# Doormio.net
KiCad netlist of a schematic drawn in EAGLE
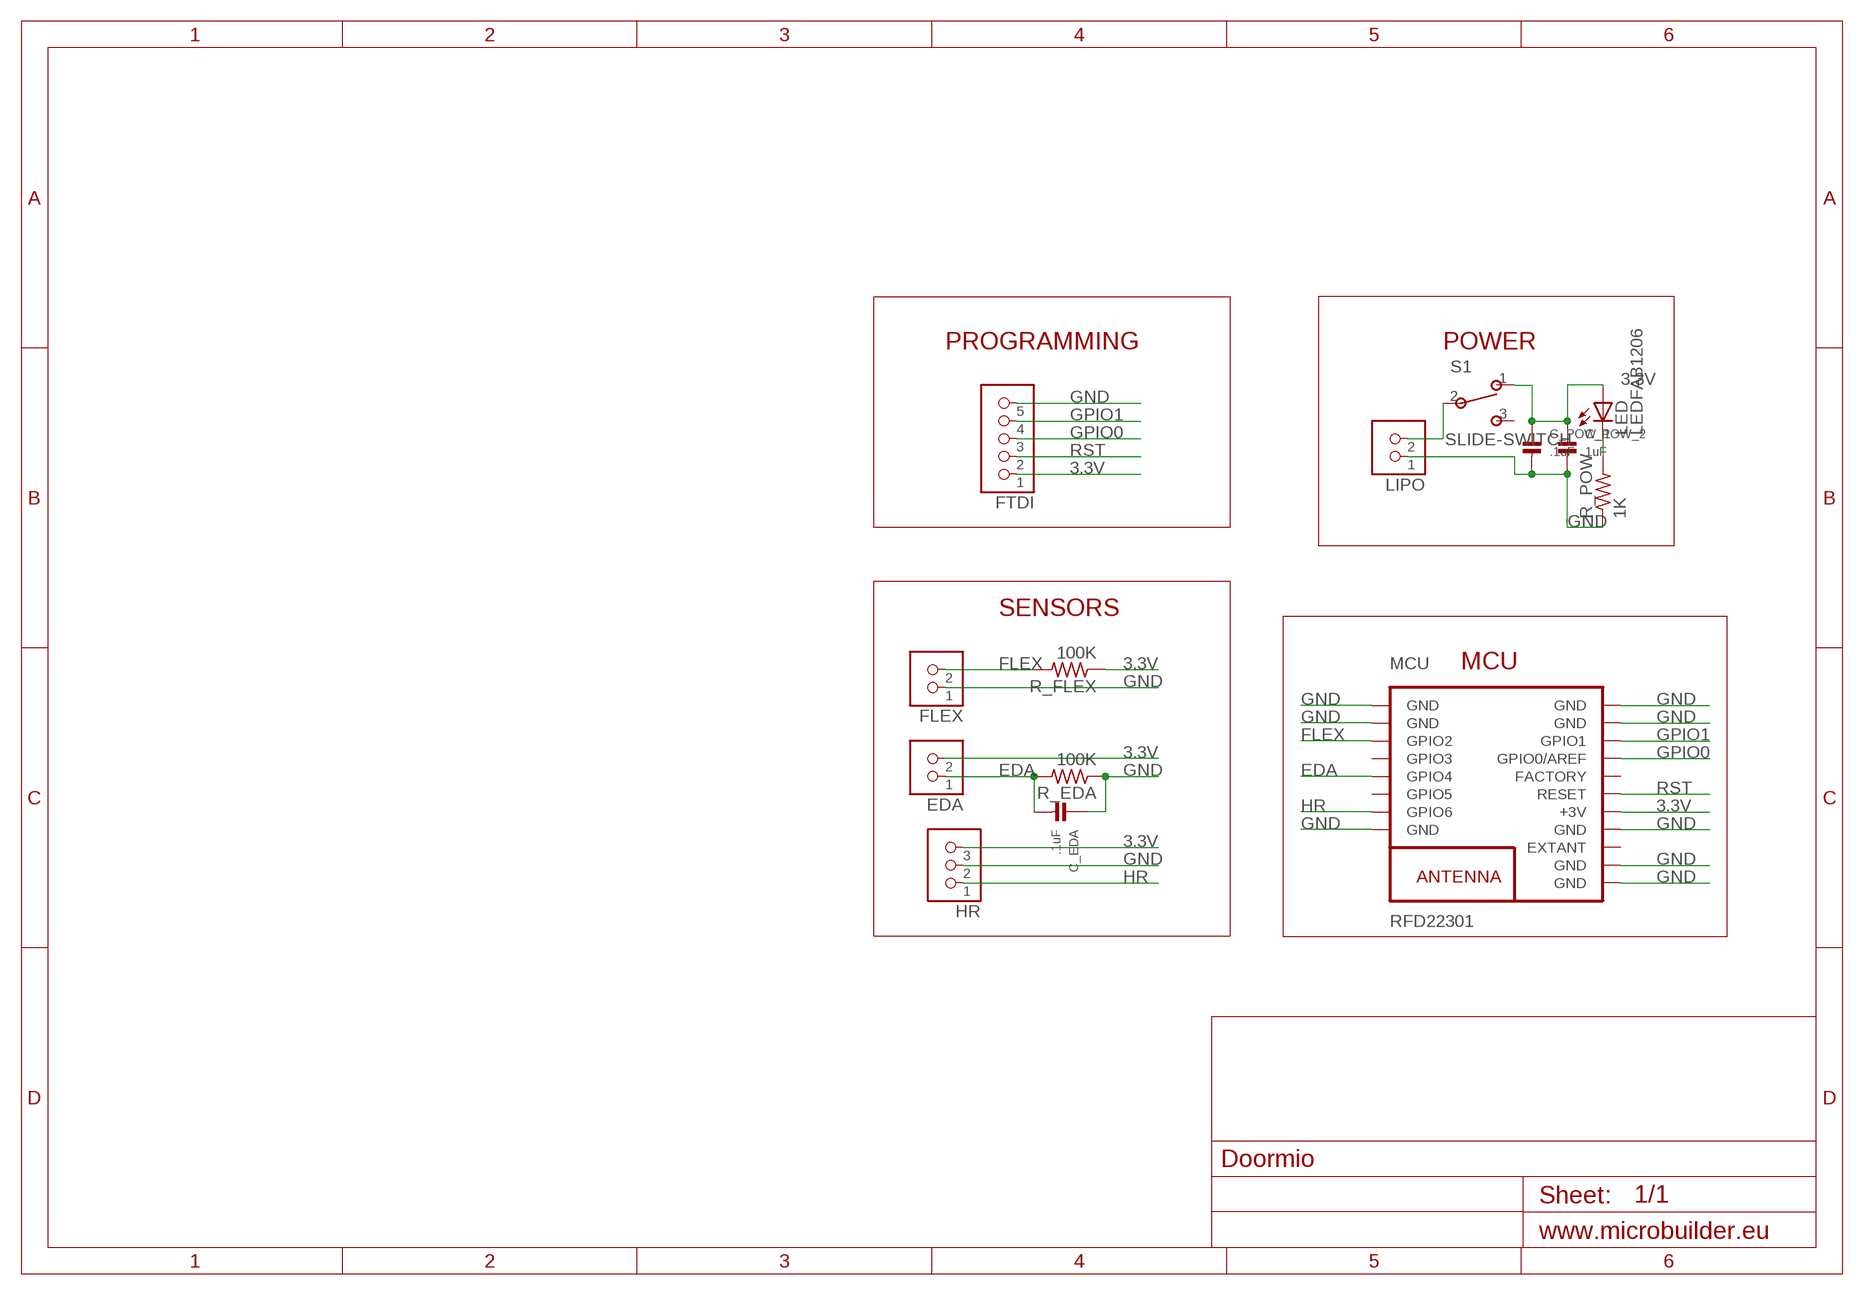
[diagram p0: schematic, sheet 1]

(export (version "E")
  (design (tool "Eeschema 10.0.6"))
  (components
    (comp (ref "C_EDA")
      (value ".1uF")
      (footprint "eagle-import:0603")
      (libsource (lib "eagle-import") (part "CAP_CERAMIC0603"))
    )
    (comp (ref "C_POW_1")
      (value ".1uF")
      (footprint "eagle-import:0603")
      (libsource (lib "eagle-import") (part "CAP_CERAMIC0603"))
    )
    (comp (ref "C_POW_2")
      (value "1uF")
      (footprint "eagle-import:0603")
      (libsource (lib "eagle-import") (part "CAP_CERAMIC0603"))
    )
    (comp (ref "EDA")
      (value "1X2-SMD-HEADER")
      (footprint "eagle-import:1X02SMD")
      (libsource (lib "eagle-import") (part "1X2-SMD-HEADER"))
    )
    (comp (ref "FLEX")
      (value "1X2-SMD-HEADER")
      (footprint "eagle-import:1X02SMD")
      (libsource (lib "eagle-import") (part "1X2-SMD-HEADER"))
    )
    (comp (ref "FTDI")
      (value "1X5-SMD-HEADER")
      (footprint "eagle-import:1X05SMD")
      (libsource (lib "eagle-import") (part "1X5-SMD-HEADER"))
    )
    (comp (ref "HR")
      (value "1X3-SMD-HEADER")
      (footprint "eagle-import:1X03SMD")
      (libsource (lib "eagle-import") (part "1X3-SMD-HEADER"))
    )
    (comp (ref "LED")
      (value "LEDFAB1206")
      (footprint "eagle-import:LED1206FAB")
      (libsource (lib "eagle-import") (part "LEDFAB1206"))
    )
    (comp (ref "LIPO")
      (value "1X2-SMD-HEADER")
      (footprint "eagle-import:1X02SMD")
      (libsource (lib "eagle-import") (part "1X2-SMD-HEADER"))
    )
    (comp (ref "MCU")
      (value "RFD22301")
      (footprint "eagle-import:RFD22301")
      (libsource (lib "eagle-import") (part "RFD22301"))
    )
    (comp (ref "R_EDA")
      (value "100K")
      (footprint "eagle-import:R0603")
      (libsource (lib "eagle-import") (part "R-US_R0603"))
    )
    (comp (ref "R_FLEX")
      (value "100K")
      (footprint "eagle-import:R0603")
      (libsource (lib "eagle-import") (part "R-US_R0603"))
    )
    (comp (ref "R_POW")
      (value "1K")
      (footprint "eagle-import:R0603")
      (libsource (lib "eagle-import") (part "R-US_R0603"))
    )
    (comp (ref "S1")
      (value "SLIDE-SWITCH")
      (footprint "eagle-import:AYZ0102AGRLC")
      (libsource (lib "eagle-import") (part "SLIDE-SWITCH"))
    )
  )
  (nets
    (net (code "1") (name "/3.3V") (class "Default")
      (node (ref "C_POW_1") (pin "1") (pinfunction "P$1_1") (pintype "passive"))
      (node (ref "C_POW_2") (pin "1") (pinfunction "P$1_1") (pintype "passive"))
      (node (ref "EDA") (pin "VCC") (pinfunction "2_VCC") (pintype "passive"))
      (node (ref "FTDI") (pin "1") (pinfunction "1_1") (pintype "passive"))
      (node (ref "HR") (pin "3") (pinfunction "3_3") (pintype "passive"))
      (node (ref "LED") (pin "1") (pinfunction "A_1") (pintype "passive"))
      (node (ref "MCU") (pin "13") (pinfunction "+3V_13") (pintype "power_in"))
      (node (ref "R_FLEX") (pin "1") (pinfunction "1_1") (pintype "passive"))
      (node (ref "S1") (pin "1") (pinfunction "1_1") (pintype "bidirectional"))
    )
    (net (code "2") (name "/EDA") (class "Default")
      (node (ref "C_EDA") (pin "2") (pinfunction "P$2_2") (pintype "passive"))
      (node (ref "EDA") (pin "GND") (pinfunction "1_GND") (pintype "passive"))
      (node (ref "MCU") (pin "5") (pinfunction "GPIO4_5") (pintype "bidirectional"))
      (node (ref "R_EDA") (pin "2") (pinfunction "2_2") (pintype "passive"))
    )
    (net (code "3") (name "/FLEX") (class "Default")
      (node (ref "FLEX") (pin "VCC") (pinfunction "2_VCC") (pintype "passive"))
      (node (ref "MCU") (pin "3") (pinfunction "GPIO2_3") (pintype "bidirectional"))
      (node (ref "R_FLEX") (pin "2") (pinfunction "2_2") (pintype "passive"))
    )
    (net (code "4") (name "/GND") (class "Default")
      (node (ref "C_EDA") (pin "1") (pinfunction "P$1_1") (pintype "passive"))
      (node (ref "C_POW_1") (pin "2") (pinfunction "P$2_2") (pintype "passive"))
      (node (ref "C_POW_2") (pin "2") (pinfunction "P$2_2") (pintype "passive"))
      (node (ref "FLEX") (pin "GND") (pinfunction "1_GND") (pintype "passive"))
      (node (ref "FTDI") (pin "5") (pinfunction "5_5") (pintype "passive"))
      (node (ref "HR") (pin "2") (pinfunction "2_2") (pintype "passive"))
      (node (ref "LIPO") (pin "GND") (pinfunction "1_GND") (pintype "passive"))
      (node (ref "MCU") (pin "1") (pinfunction "GND_1") (pintype "power_in"))
      (node (ref "MCU") (pin "10") (pinfunction "GND_10") (pintype "power_in"))
      (node (ref "MCU") (pin "12") (pinfunction "GND_12") (pintype "power_in"))
      (node (ref "MCU") (pin "18") (pinfunction "GND_18") (pintype "power_in"))
      (node (ref "MCU") (pin "19") (pinfunction "GND_19") (pintype "power_in"))
      (node (ref "MCU") (pin "2") (pinfunction "GND_2") (pintype "power_in"))
      (node (ref "MCU") (pin "8") (pinfunction "GND_8") (pintype "power_in"))
      (node (ref "MCU") (pin "9") (pinfunction "GND_9") (pintype "power_in"))
      (node (ref "R_EDA") (pin "1") (pinfunction "1_1") (pintype "passive"))
      (node (ref "R_POW") (pin "1") (pinfunction "1_1") (pintype "passive"))
    )
    (net (code "5") (name "/GPIO0") (class "Default")
      (node (ref "FTDI") (pin "3") (pinfunction "3_3") (pintype "passive"))
      (node (ref "MCU") (pin "16") (pinfunction "GPIO0/AREF_16") (pintype "bidirectional"))
    )
    (net (code "6") (name "/GPIO1") (class "Default")
      (node (ref "FTDI") (pin "4") (pinfunction "4_4") (pintype "passive"))
      (node (ref "MCU") (pin "17") (pinfunction "GPIO1_17") (pintype "bidirectional"))
    )
    (net (code "7") (name "/HR") (class "Default")
      (node (ref "HR") (pin "1") (pinfunction "1_1") (pintype "passive"))
      (node (ref "MCU") (pin "7") (pinfunction "GPIO6_7") (pintype "bidirectional"))
    )
    (net (code "8") (name "/RST") (class "Default")
      (node (ref "FTDI") (pin "2") (pinfunction "2_2") (pintype "passive"))
      (node (ref "MCU") (pin "14") (pinfunction "RESET_14") (pintype "bidirectional"))
    )
    (net (code "9") (name "Net-(LED-C)") (class "Default")
      (node (ref "LED") (pin "2") (pinfunction "C_2") (pintype "passive"))
      (node (ref "R_POW") (pin "2") (pinfunction "2_2") (pintype "passive"))
    )
    (net (code "10") (name "Net-(LIPO-2)") (class "Default")
      (node (ref "LIPO") (pin "VCC") (pinfunction "2_VCC") (pintype "passive"))
      (node (ref "S1") (pin "2") (pinfunction "2_2") (pintype "bidirectional"))
    )
    (net (code "11") (name "unconnected-(MCU-EXTANT-Pad11)") (class "Default")
      (node (ref "MCU") (pin "11") (pinfunction "EXTANT_11") (pintype "no_connect"))
    )
    (net (code "12") (name "unconnected-(MCU-FACTORY-Pad15)") (class "Default")
      (node (ref "MCU") (pin "15") (pinfunction "FACTORY_15") (pintype "bidirectional"))
    )
    (net (code "13") (name "unconnected-(MCU-GPIO3-Pad4)") (class "Default")
      (node (ref "MCU") (pin "4") (pinfunction "GPIO3_4") (pintype "bidirectional"))
    )
    (net (code "14") (name "unconnected-(MCU-GPIO5-Pad6)") (class "Default")
      (node (ref "MCU") (pin "6") (pinfunction "GPIO5_6") (pintype "bidirectional"))
    )
    (net (code "15") (name "unconnected-(S1-Pad3)") (class "Default")
      (node (ref "S1") (pin "3") (pinfunction "3_3") (pintype "bidirectional"))
    )
  )
)
